# Xplained_RFM98W.net
KiCad netlist of a schematic drawn in EAGLE
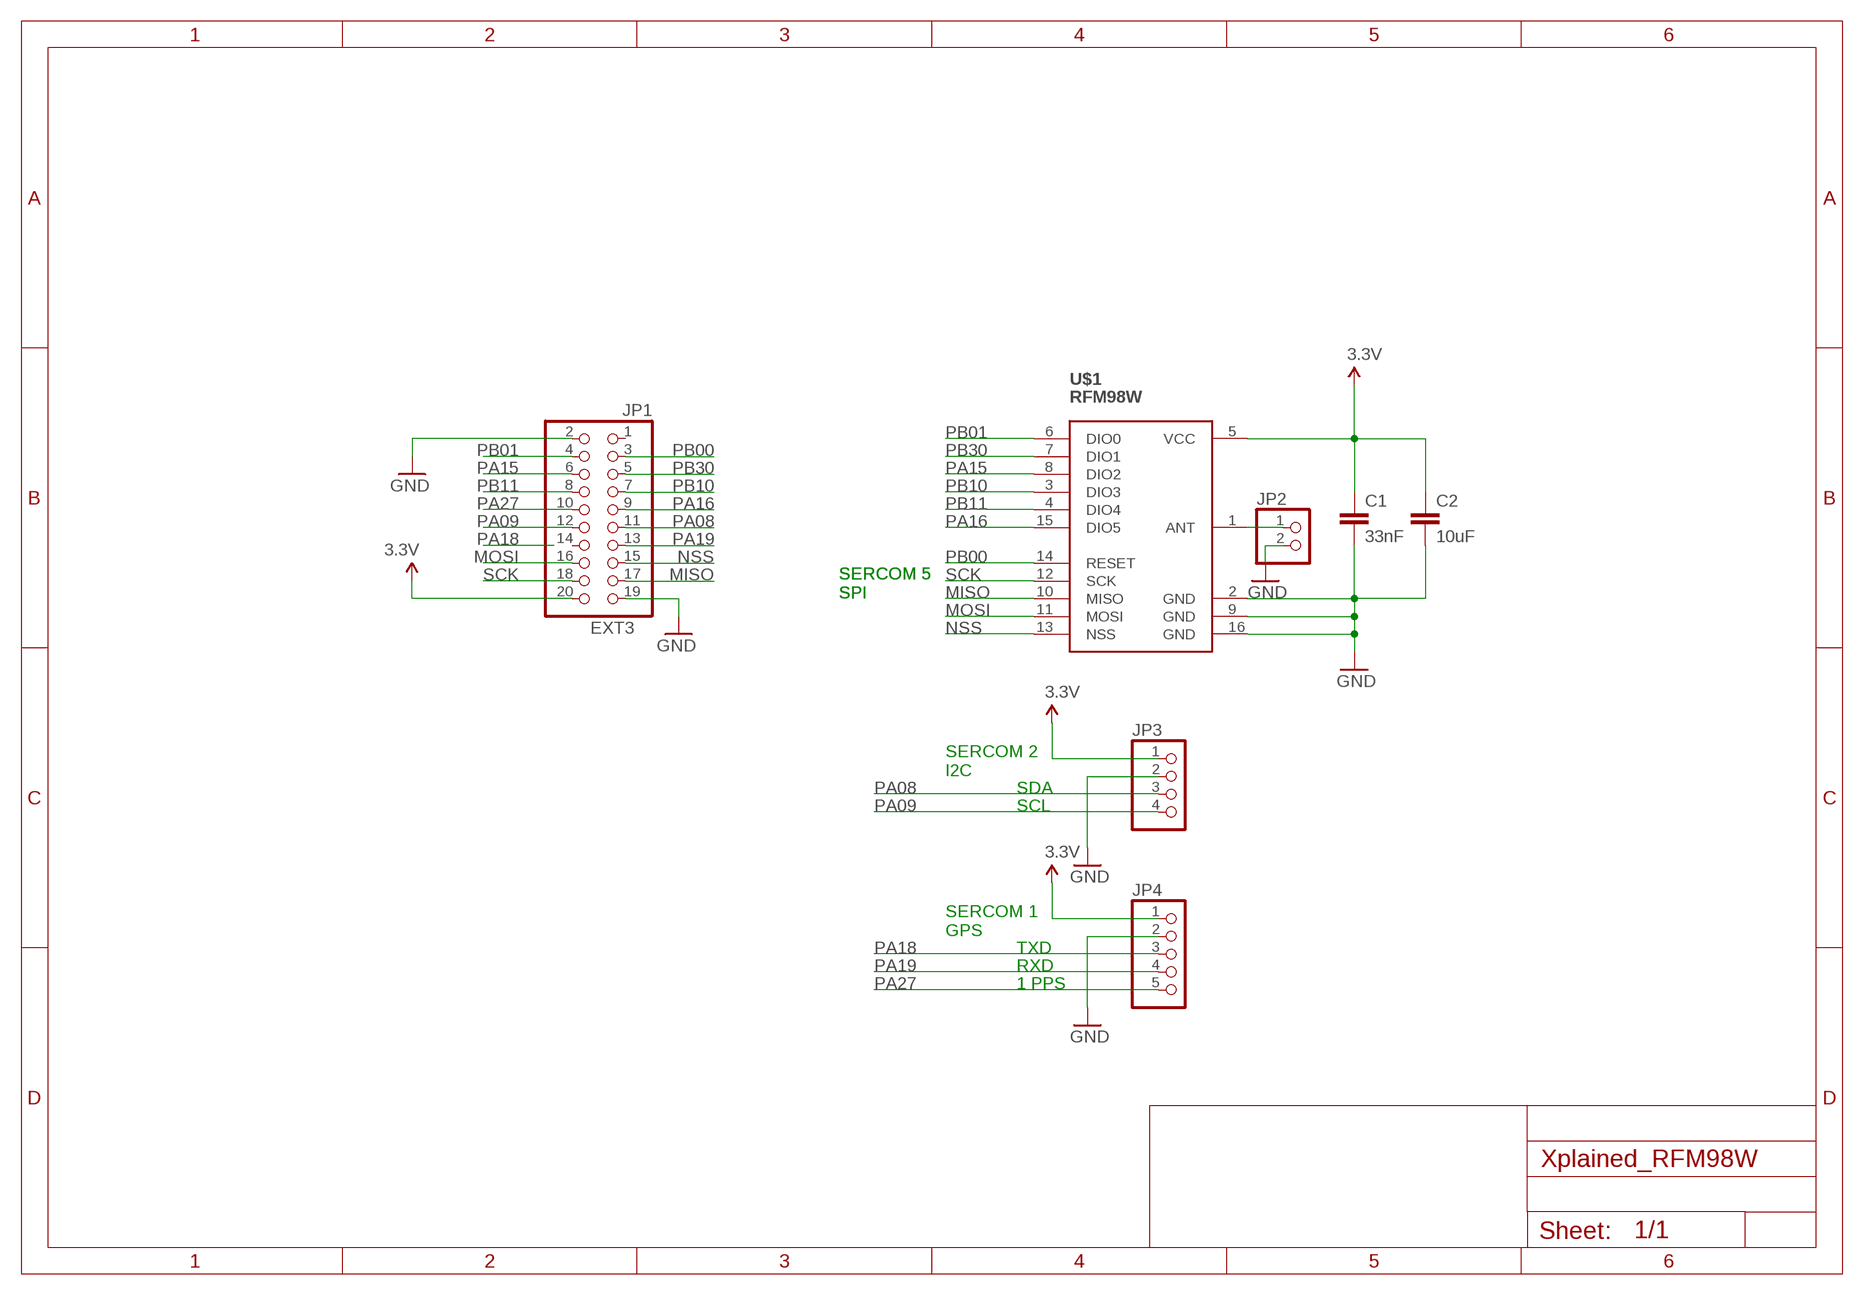
[diagram p0: schematic, sheet 1]

(export (version "E")
  (design (tool "Eeschema 10.0.6"))
  (components
    (comp (ref "C1")
      (value "33nF")
      (footprint "eagle-import:0603-CAP")
      (libsource (lib "eagle-import") (part "CAP0603-CAP"))
    )
    (comp (ref "C2")
      (value "10uF")
      (footprint "eagle-import:0603-CAP")
      (libsource (lib "eagle-import") (part "CAP0603-CAP"))
    )
    (comp (ref "JP1")
      (value "EXT3")
      (footprint "eagle-import:2X10_90")
      (libsource (lib "eagle-import") (part "PINHD-2X10/90"))
    )
    (comp (ref "JP2")
      (value "PINHD-1X2")
      (footprint "eagle-import:1X02")
      (libsource (lib "eagle-import") (part "PINHD-1X2"))
    )
    (comp (ref "JP3")
      (value "PINHD-1X4/90")
      (footprint "eagle-import:1X04_90")
      (libsource (lib "eagle-import") (part "PINHD-1X4/90"))
    )
    (comp (ref "JP4")
      (value "PINHD-1X5/90")
      (footprint "eagle-import:1X05_90")
      (libsource (lib "eagle-import") (part "PINHD-1X5/90"))
    )
    (comp (ref "U$1")
      (value "RFM98W")
      (footprint "eagle-import:MODULE_16X16_16PIN")
      (libsource (lib "eagle-import") (part "RFM66W_69HCW_9XW"))
    )
  )
  (nets
    (net (code "1") (name "/MISO") (class "Default")
      (node (ref "JP1") (pin "17") (pinfunction "17_17") (pintype "passive"))
      (node (ref "U$1") (pin "10") (pinfunction "MISO_10") (pintype "bidirectional"))
    )
    (net (code "2") (name "/MOSI") (class "Default")
      (node (ref "JP1") (pin "16") (pinfunction "16_16") (pintype "passive"))
      (node (ref "U$1") (pin "11") (pinfunction "MOSI_11") (pintype "bidirectional"))
    )
    (net (code "3") (name "/NSS") (class "Default")
      (node (ref "JP1") (pin "15") (pinfunction "15_15") (pintype "passive"))
      (node (ref "U$1") (pin "13") (pinfunction "NSS_13") (pintype "bidirectional"))
    )
    (net (code "4") (name "/PA08") (class "Default")
      (node (ref "JP1") (pin "11") (pinfunction "11_11") (pintype "passive"))
      (node (ref "JP3") (pin "3") (pinfunction "3_3") (pintype "passive"))
    )
    (net (code "5") (name "/PA09") (class "Default")
      (node (ref "JP1") (pin "12") (pinfunction "12_12") (pintype "passive"))
      (node (ref "JP3") (pin "4") (pinfunction "4_4") (pintype "passive"))
    )
    (net (code "6") (name "/PA15") (class "Default")
      (node (ref "JP1") (pin "6") (pinfunction "6_6") (pintype "passive"))
      (node (ref "U$1") (pin "8") (pinfunction "DIO2_8") (pintype "bidirectional"))
    )
    (net (code "7") (name "/PA16") (class "Default")
      (node (ref "JP1") (pin "9") (pinfunction "9_9") (pintype "passive"))
      (node (ref "U$1") (pin "15") (pinfunction "DIO5_15") (pintype "bidirectional"))
    )
    (net (code "8") (name "/PA18") (class "Default")
      (node (ref "JP4") (pin "3") (pinfunction "3_3") (pintype "passive"))
    )
    (net (code "9") (name "/PA19") (class "Default")
      (node (ref "JP1") (pin "13") (pinfunction "13_13") (pintype "passive"))
      (node (ref "JP4") (pin "4") (pinfunction "4_4") (pintype "passive"))
    )
    (net (code "10") (name "/PA27") (class "Default")
      (node (ref "JP1") (pin "10") (pinfunction "10_10") (pintype "passive"))
      (node (ref "JP4") (pin "5") (pinfunction "5_5") (pintype "passive"))
    )
    (net (code "11") (name "/PB00") (class "Default")
      (node (ref "JP1") (pin "3") (pinfunction "3_3") (pintype "passive"))
      (node (ref "U$1") (pin "14") (pinfunction "RESET_14") (pintype "bidirectional"))
    )
    (net (code "12") (name "/PB01") (class "Default")
      (node (ref "JP1") (pin "4") (pinfunction "4_4") (pintype "passive"))
      (node (ref "U$1") (pin "6") (pinfunction "DIO0_6") (pintype "bidirectional"))
    )
    (net (code "13") (name "/PB10") (class "Default")
      (node (ref "JP1") (pin "7") (pinfunction "7_7") (pintype "passive"))
      (node (ref "U$1") (pin "3") (pinfunction "DIO3_3") (pintype "bidirectional"))
    )
    (net (code "14") (name "/PB11") (class "Default")
      (node (ref "JP1") (pin "8") (pinfunction "8_8") (pintype "passive"))
      (node (ref "U$1") (pin "4") (pinfunction "DIO4_4") (pintype "bidirectional"))
    )
    (net (code "15") (name "/PB30") (class "Default")
      (node (ref "JP1") (pin "5") (pinfunction "5_5") (pintype "passive"))
      (node (ref "U$1") (pin "7") (pinfunction "DIO1_7") (pintype "bidirectional"))
    )
    (net (code "16") (name "/SCK") (class "Default")
      (node (ref "JP1") (pin "18") (pinfunction "18_18") (pintype "passive"))
      (node (ref "U$1") (pin "12") (pinfunction "SCK_12") (pintype "bidirectional"))
    )
    (net (code "17") (name "3.3V") (class "Default")
      (node (ref "C1") (pin "1") (pinfunction "1_1") (pintype "passive"))
      (node (ref "C2") (pin "1") (pinfunction "1_1") (pintype "passive"))
      (node (ref "JP1") (pin "20") (pinfunction "20_20") (pintype "passive"))
      (node (ref "JP3") (pin "1") (pinfunction "1_1") (pintype "passive"))
      (node (ref "JP4") (pin "1") (pinfunction "1_1") (pintype "passive"))
      (node (ref "U$1") (pin "5") (pinfunction "VCC_5") (pintype "bidirectional"))
    )
    (net (code "18") (name "GND") (class "Default")
      (node (ref "C1") (pin "2") (pinfunction "2_2") (pintype "passive"))
      (node (ref "C2") (pin "2") (pinfunction "2_2") (pintype "passive"))
      (node (ref "JP1") (pin "19") (pinfunction "19_19") (pintype "passive"))
      (node (ref "JP1") (pin "2") (pinfunction "2_2") (pintype "passive"))
      (node (ref "JP2") (pin "2") (pinfunction "2_2") (pintype "passive"))
      (node (ref "JP3") (pin "2") (pinfunction "2_2") (pintype "passive"))
      (node (ref "JP4") (pin "2") (pinfunction "2_2") (pintype "passive"))
      (node (ref "U$1") (pin "16") (pinfunction "GND_16") (pintype "bidirectional"))
      (node (ref "U$1") (pin "2") (pinfunction "GND_2") (pintype "bidirectional"))
      (node (ref "U$1") (pin "9") (pinfunction "GND_9") (pintype "bidirectional"))
    )
    (net (code "19") (name "Net-(U$1-ANT)") (class "Default")
      (node (ref "JP2") (pin "1") (pinfunction "1_1") (pintype "passive"))
      (node (ref "U$1") (pin "1") (pinfunction "ANT_1") (pintype "bidirectional"))
    )
    (net (code "20") (name "unconnected-(JP1-Pad1)") (class "Default")
      (node (ref "JP1") (pin "1") (pinfunction "1_1") (pintype "passive"))
    )
    (net (code "21") (name "unconnected-(JP1-Pad14)") (class "Default")
      (node (ref "JP1") (pin "14") (pinfunction "14_14") (pintype "passive"))
    )
  )
)
